# Wired_Mouse.net
KiCad netlist of a schematic drawn in EAGLE
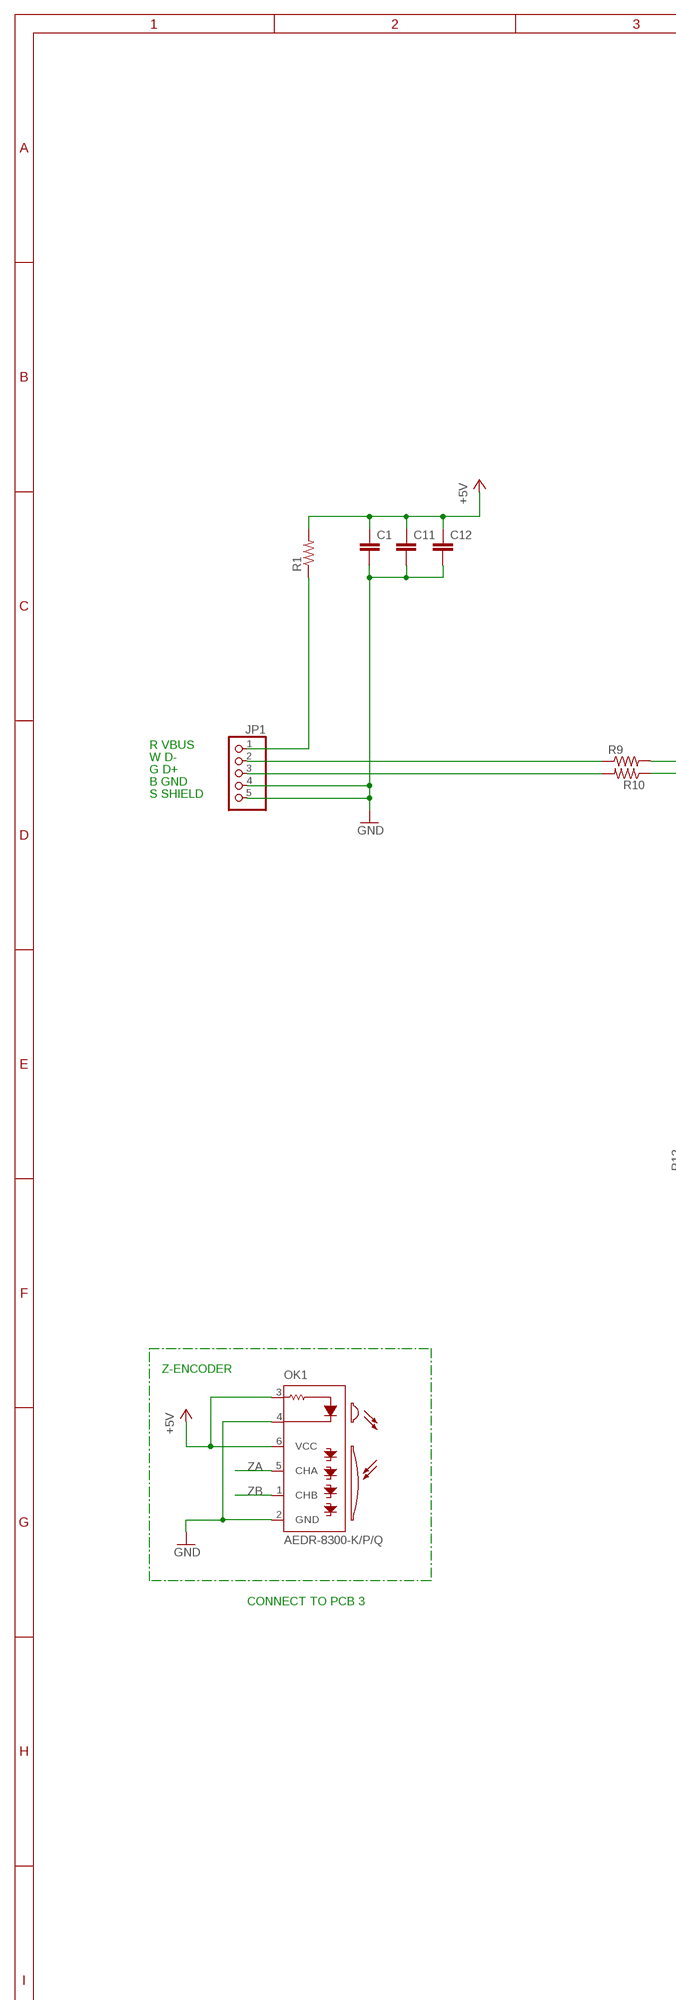
[diagram p0: schematic, sheet 1, part 1 of 2]
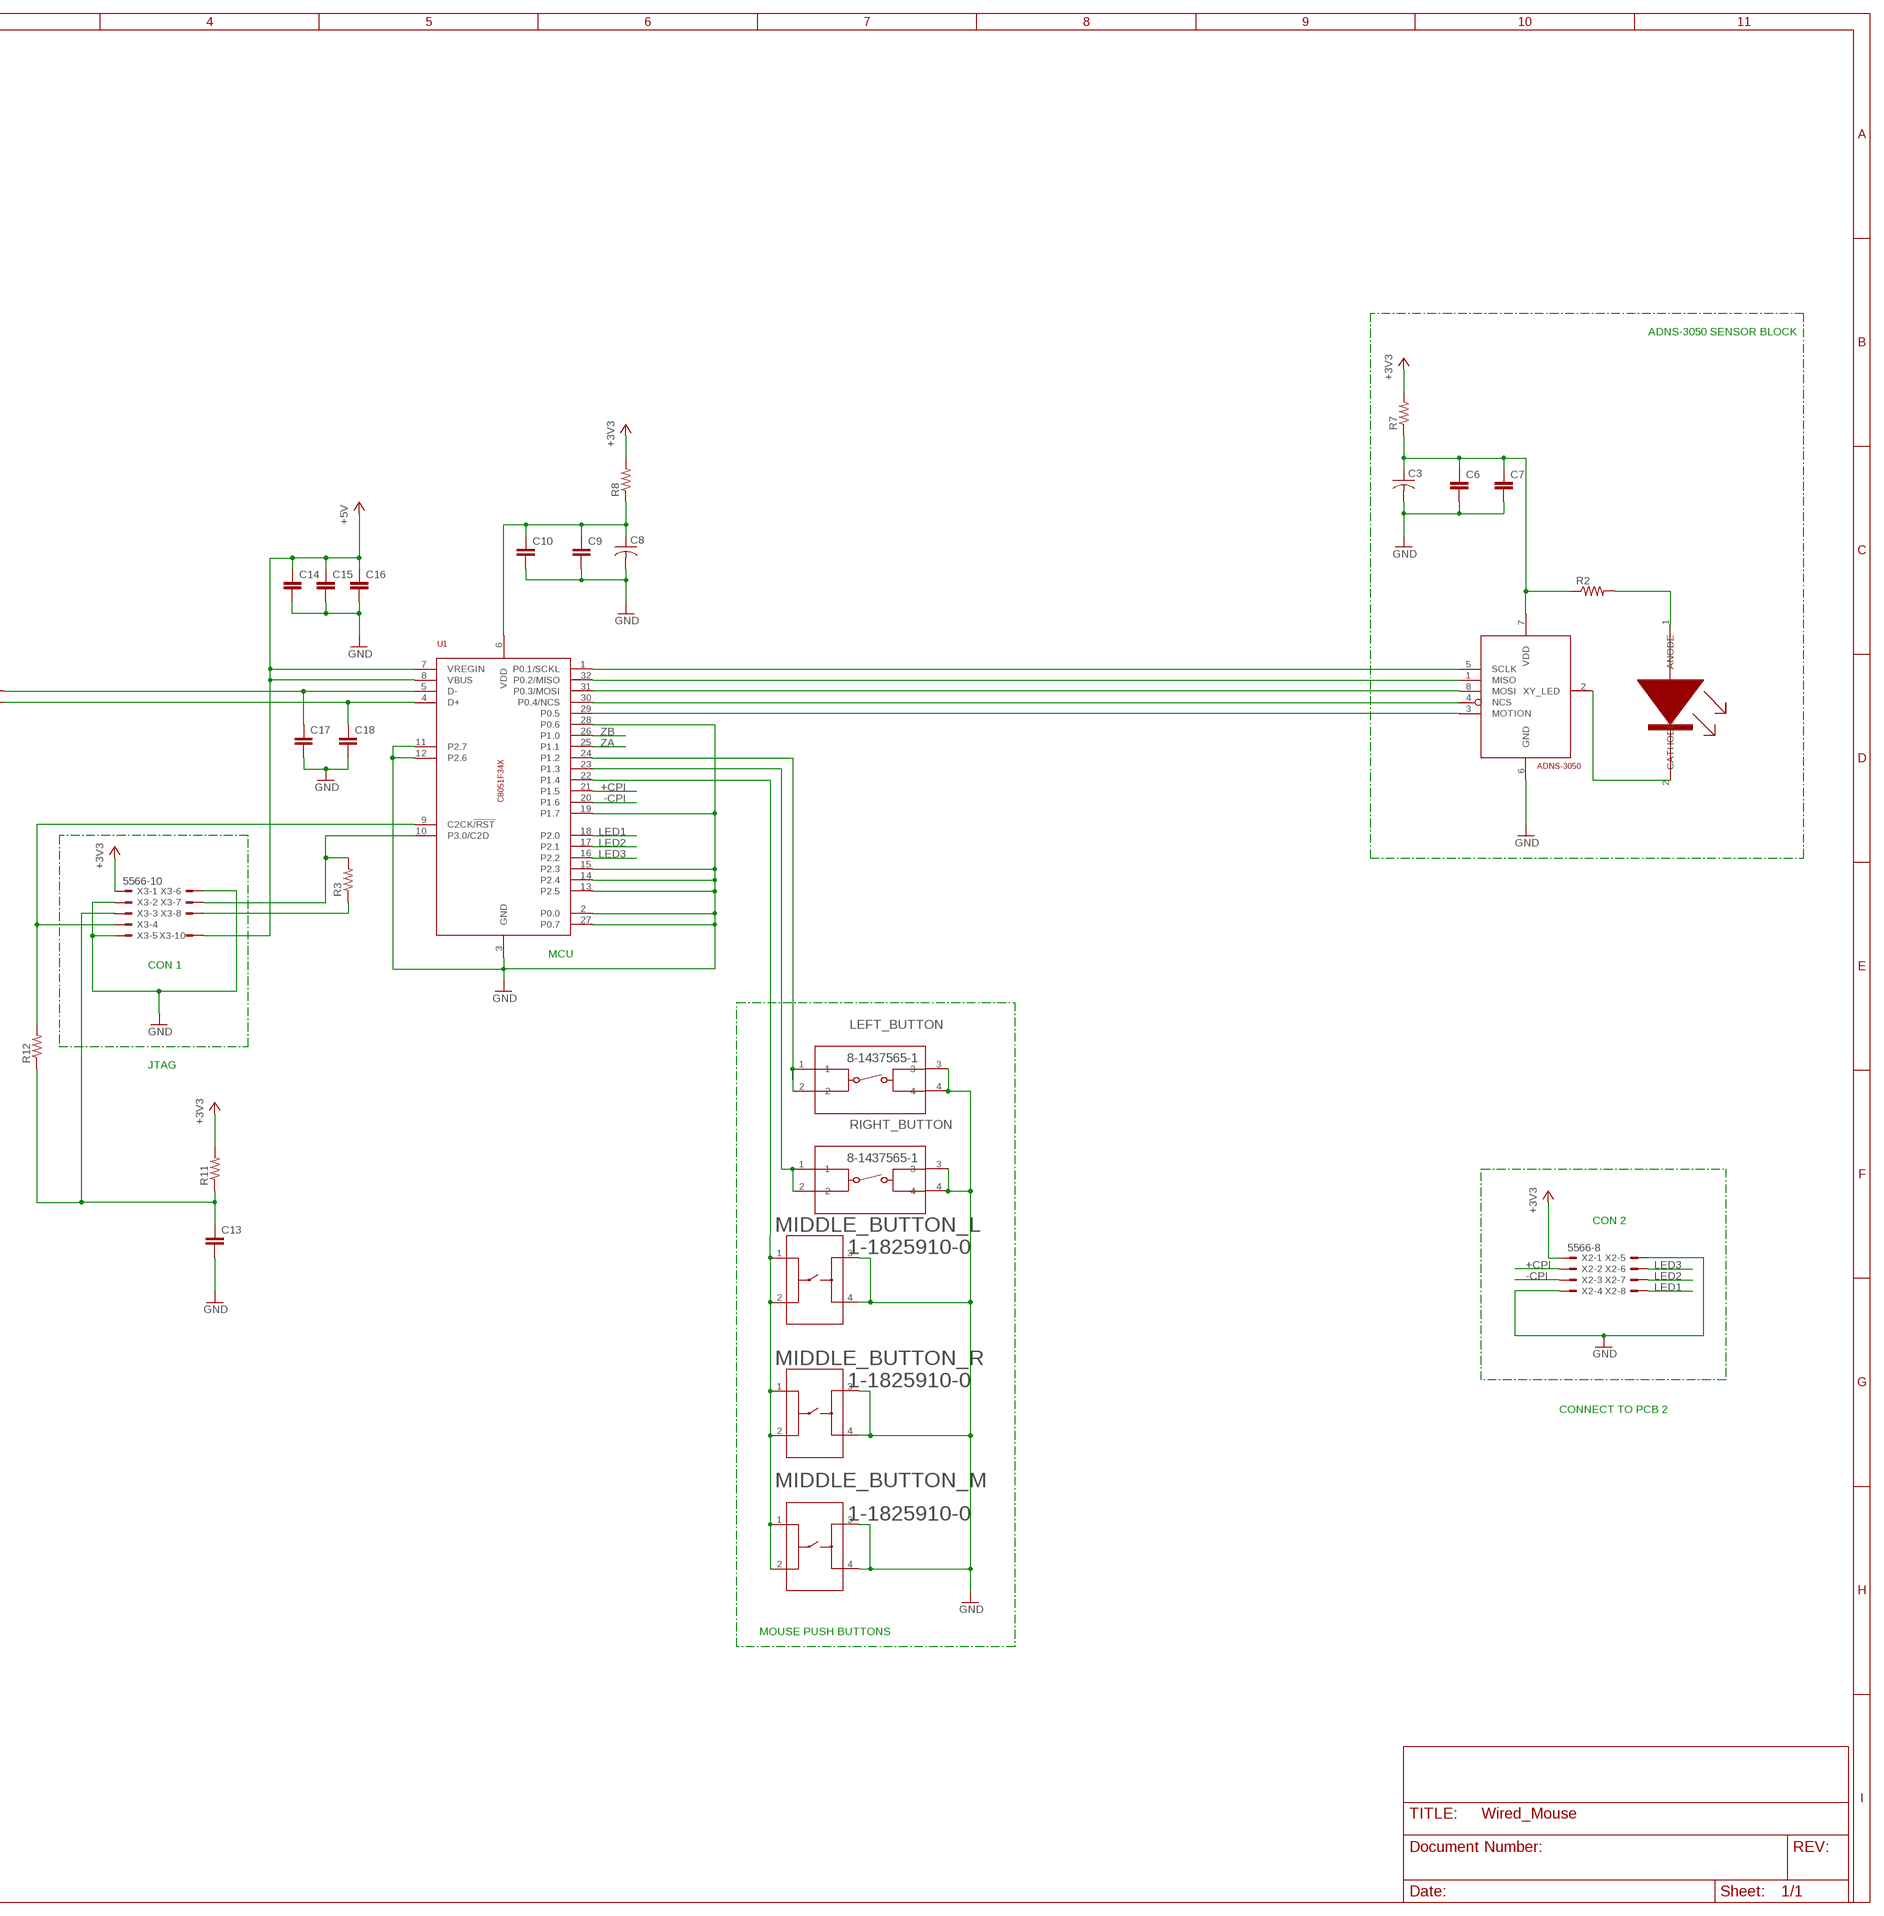
[diagram p1: schematic, sheet 1, part 2 of 2]

(export (version "E")
  (design (tool "Eeschema 10.0.6"))
  (components
    (comp (ref "C1")
      (value "C-EUC0201")
      (footprint "eagle-import:C0201")
      (libsource (lib "eagle-import") (part "C-EUC0201"))
    )
    (comp (ref "C3")
      (value "C-US025-025X050")
      (footprint "eagle-import:C025-025X050")
      (libsource (lib "eagle-import") (part "C-US025-025X050"))
    )
    (comp (ref "C6")
      (value "C-EUC0201")
      (footprint "eagle-import:C0201")
      (libsource (lib "eagle-import") (part "C-EUC0201"))
    )
    (comp (ref "C7")
      (value "C-EUC0201")
      (footprint "eagle-import:C0201")
      (libsource (lib "eagle-import") (part "C-EUC0201"))
    )
    (comp (ref "C8")
      (value "C-US025-025X050")
      (footprint "eagle-import:C025-025X050")
      (libsource (lib "eagle-import") (part "C-US025-025X050"))
    )
    (comp (ref "C9")
      (value "C-EUC0201")
      (footprint "eagle-import:C0201")
      (libsource (lib "eagle-import") (part "C-EUC0201"))
    )
    (comp (ref "C10")
      (value "C-EUC0201")
      (footprint "eagle-import:C0201")
      (libsource (lib "eagle-import") (part "C-EUC0201"))
    )
    (comp (ref "C11")
      (value "C-EUC0201")
      (footprint "eagle-import:C0201")
      (libsource (lib "eagle-import") (part "C-EUC0201"))
    )
    (comp (ref "C12")
      (value "C-EUC0201")
      (footprint "eagle-import:C0201")
      (libsource (lib "eagle-import") (part "C-EUC0201"))
    )
    (comp (ref "C13")
      (value "C-EUC0201")
      (footprint "eagle-import:C0201")
      (libsource (lib "eagle-import") (part "C-EUC0201"))
    )
    (comp (ref "C14")
      (value "C-EUC0201")
      (footprint "eagle-import:C0201")
      (libsource (lib "eagle-import") (part "C-EUC0201"))
    )
    (comp (ref "C15")
      (value "C-EUC0201")
      (footprint "eagle-import:C0201")
      (libsource (lib "eagle-import") (part "C-EUC0201"))
    )
    (comp (ref "C16")
      (value "C-EUC0201")
      (footprint "eagle-import:C0201")
      (libsource (lib "eagle-import") (part "C-EUC0201"))
    )
    (comp (ref "C17")
      (value "C-EUC0201")
      (footprint "eagle-import:C0201")
      (libsource (lib "eagle-import") (part "C-EUC0201"))
    )
    (comp (ref "C18")
      (value "C-EUC0201")
      (footprint "eagle-import:C0201")
      (libsource (lib "eagle-import") (part "C-EUC0201"))
    )
    (comp (ref "JP1")
      (value "PINHD-1X5/90")
      (footprint "eagle-import:1X05_90")
      (fields (field (name "SPICEPREFIX") "X"))
      (libsource (lib "eagle-import") (part "PINHD-1X5/90"))
    )
    (comp (ref "LEFT_BUTTON")
      (value "8-1437565-1")
      (footprint "eagle-import:SW4_1437565")
      (fields (field (name "COPYRIGHT") "Copyright (C) 2016 Accelerated Designs. All rights reserved"))
      (libsource (lib "eagle-import") (part "8-1437565-1"))
    )
    (comp (ref "MIDDLE_BUTTON_L")
      (value "1-1825910-0")
      (footprint "eagle-import:SWITCH_1-1825910-0")
      (fields (field (name "COPYRIGHT") "Copyright (C) 2016 Accelerated Designs. All rights reserved"))
      (libsource (lib "eagle-import") (part "1-1825910-0"))
    )
    (comp (ref "MIDDLE_BUTTON_M")
      (value "1-1825910-0")
      (footprint "eagle-import:SWITCH_1-1825910-0")
      (fields (field (name "COPYRIGHT") "Copyright (C) 2016 Accelerated Designs. All rights reserved"))
      (libsource (lib "eagle-import") (part "1-1825910-0"))
    )
    (comp (ref "MIDDLE_BUTTON_R")
      (value "1-1825910-0")
      (footprint "eagle-import:SWITCH_1-1825910-0")
      (fields (field (name "COPYRIGHT") "Copyright (C) 2016 Accelerated Designs. All rights reserved"))
      (libsource (lib "eagle-import") (part "1-1825910-0"))
    )
    (comp (ref "OK1")
      (value "AEDR-8300-K/P/Q")
      (footprint "eagle-import:AEDR-8300")
      (fields
        (field (name "MF") "AGILENT TECHNOLOGIES")
        (field (name "MPN") "AEDR-8300-1P2")
        (field (name "SPICEPREFIX") "X")
      )
      (libsource (lib "eagle-import") (part "AEDR-8300-K/P/Q"))
    )
    (comp (ref "R1")
      (value "R-US_0204/7")
      (footprint "eagle-import:0204_7")
      (libsource (lib "eagle-import") (part "R-US_0204/7"))
    )
    (comp (ref "R2")
      (value "R-US_0204/7")
      (footprint "eagle-import:0204_7")
      (libsource (lib "eagle-import") (part "R-US_0204/7"))
    )
    (comp (ref "R3")
      (value "R-US_0204/7")
      (footprint "eagle-import:0204_7")
      (libsource (lib "eagle-import") (part "R-US_0204/7"))
    )
    (comp (ref "R7")
      (value "R-US_0204/7")
      (footprint "eagle-import:0204_7")
      (libsource (lib "eagle-import") (part "R-US_0204/7"))
    )
    (comp (ref "R8")
      (value "R-US_0204/7")
      (footprint "eagle-import:0204_7")
      (libsource (lib "eagle-import") (part "R-US_0204/7"))
    )
    (comp (ref "R9")
      (value "R-US_0204/7")
      (footprint "eagle-import:0204_7")
      (libsource (lib "eagle-import") (part "R-US_0204/7"))
    )
    (comp (ref "R10")
      (value "R-US_0204/7")
      (footprint "eagle-import:0204_7")
      (libsource (lib "eagle-import") (part "R-US_0204/7"))
    )
    (comp (ref "R11")
      (value "R-US_0204/7")
      (footprint "eagle-import:0204_7")
      (libsource (lib "eagle-import") (part "R-US_0204/7"))
    )
    (comp (ref "R12")
      (value "R-US_0204/7")
      (footprint "eagle-import:0204_7")
      (libsource (lib "eagle-import") (part "R-US_0204/7"))
    )
    (comp (ref "RIGHT_BUTTON")
      (value "8-1437565-1")
      (footprint "eagle-import:SW4_1437565")
      (fields (field (name "COPYRIGHT") "Copyright (C) 2016 Accelerated Designs. All rights reserved"))
      (libsource (lib "eagle-import") (part "8-1437565-1"))
    )
    (comp (ref "U$1")
      (value "ADNS_3050THROUGH_HOLE")
      (footprint "eagle-import:DIP1279W50P200L985H450Q8B")
      (fields (field (name "SPICEPREFIX") "X"))
      (libsource (lib "eagle-import") (part "ADNS_3050THROUGH_HOLE"))
    )
    (comp (ref "U$2")
      (value "C8051F34XSURFACE-MOUNT")
      (footprint "eagle-import:QFP80P900X900X160-32N")
      (fields (field (name "SPICEPREFIX") "X"))
      (libsource (lib "eagle-import") (part "C8051F34XSURFACE-MOUNT"))
    )
    (comp (ref "U$3")
      (value "HLMP-EGXX_LEDTHROUGH_HOLE")
      (footprint "eagle-import:LEDRD254W50D500H871B")
      (fields (field (name "SPICEPREFIX") "B"))
      (libsource (lib "eagle-import") (part "HLMP-EGXX_LEDTHROUGH_HOLE"))
    )
    (comp (ref "X2")
      (value "5566-8")
      (footprint "eagle-import:5566-8")
      (fields (field (name "MF") "MOLEX") (field (name "SPICEPREFIX") "X"))
      (libsource (lib "eagle-import") (part "5566-8"))
    )
    (comp (ref "X3")
      (value "5566-10")
      (footprint "eagle-import:5566-10")
      (fields (field (name "MF") "MOLEX") (field (name "SPICEPREFIX") "X"))
      (libsource (lib "eagle-import") (part "5566-10"))
    )
  )
  (nets
    (net (code "1") (name "+3V3") (class "Default")
      (node (ref "R11") (pin "2") (pinfunction "2_2") (pintype "passive"))
      (node (ref "R7") (pin "2") (pinfunction "2_2") (pintype "passive"))
      (node (ref "R8") (pin "2") (pinfunction "2_2") (pintype "passive"))
      (node (ref "X2") (pin "1") (pinfunction "S_1") (pintype "passive"))
      (node (ref "X3") (pin "1") (pinfunction "S_1") (pintype "passive"))
    )
    (net (code "2") (name "+5V") (class "Default")
      (node (ref "C1") (pin "1") (pinfunction "1_1") (pintype "passive"))
      (node (ref "C11") (pin "1") (pinfunction "1_1") (pintype "passive"))
      (node (ref "C12") (pin "1") (pinfunction "1_1") (pintype "passive"))
      (node (ref "C14") (pin "1") (pinfunction "1_1") (pintype "passive"))
      (node (ref "C15") (pin "1") (pinfunction "1_1") (pintype "passive"))
      (node (ref "C16") (pin "1") (pinfunction "1_1") (pintype "passive"))
      (node (ref "OK1") (pin "3") (pinfunction "A_3") (pintype "passive"))
      (node (ref "OK1") (pin "6") (pinfunction "VCC_6") (pintype "passive"))
      (node (ref "R1") (pin "2") (pinfunction "2_2") (pintype "passive"))
      (node (ref "U$2") (pin "7") (pinfunction "VREGIN_7") (pintype "bidirectional"))
      (node (ref "U$2") (pin "8") (pinfunction "VBUS_8") (pintype "bidirectional"))
      (node (ref "X3") (pin "10") (pinfunction "S_10") (pintype "passive"))
    )
    (net (code "3") (name "/+CPI") (class "Default")
      (node (ref "U$2") (pin "21") (pinfunction "P1.5_21") (pintype "bidirectional"))
      (node (ref "X2") (pin "2") (pinfunction "S_2") (pintype "passive"))
    )
    (net (code "4") (name "/-CPI") (class "Default")
      (node (ref "U$2") (pin "20") (pinfunction "P1.6_20") (pintype "bidirectional"))
      (node (ref "X2") (pin "3") (pinfunction "S_3") (pintype "passive"))
    )
    (net (code "5") (name "/LED1") (class "Default")
      (node (ref "U$2") (pin "18") (pinfunction "P2.0_18") (pintype "bidirectional"))
      (node (ref "X2") (pin "8") (pinfunction "S_8") (pintype "passive"))
    )
    (net (code "6") (name "/LED2") (class "Default")
      (node (ref "U$2") (pin "17") (pinfunction "P2.1_17") (pintype "bidirectional"))
      (node (ref "X2") (pin "7") (pinfunction "S_7") (pintype "passive"))
    )
    (net (code "7") (name "/LED3") (class "Default")
      (node (ref "U$2") (pin "16") (pinfunction "P2.2_16") (pintype "bidirectional"))
      (node (ref "X2") (pin "6") (pinfunction "S_6") (pintype "passive"))
    )
    (net (code "8") (name "/ZA") (class "Default")
      (node (ref "OK1") (pin "5") (pinfunction "CHA_5") (pintype "passive"))
      (node (ref "U$2") (pin "25") (pinfunction "P1.1_25") (pintype "bidirectional"))
    )
    (net (code "9") (name "/ZB") (class "Default")
      (node (ref "OK1") (pin "1") (pinfunction "CHB_1") (pintype "passive"))
      (node (ref "U$2") (pin "26") (pinfunction "P1.0_26") (pintype "bidirectional"))
    )
    (net (code "10") (name "GND") (class "Default")
      (node (ref "C1") (pin "2") (pinfunction "2_2") (pintype "passive"))
      (node (ref "C10") (pin "2") (pinfunction "2_2") (pintype "passive"))
      (node (ref "C11") (pin "2") (pinfunction "2_2") (pintype "passive"))
      (node (ref "C12") (pin "2") (pinfunction "2_2") (pintype "passive"))
      (node (ref "C13") (pin "2") (pinfunction "2_2") (pintype "passive"))
      (node (ref "C14") (pin "2") (pinfunction "2_2") (pintype "passive"))
      (node (ref "C15") (pin "2") (pinfunction "2_2") (pintype "passive"))
      (node (ref "C16") (pin "2") (pinfunction "2_2") (pintype "passive"))
      (node (ref "C17") (pin "2") (pinfunction "2_2") (pintype "passive"))
      (node (ref "C18") (pin "2") (pinfunction "2_2") (pintype "passive"))
      (node (ref "C3") (pin "2") (pinfunction "2_2") (pintype "passive"))
      (node (ref "C6") (pin "2") (pinfunction "2_2") (pintype "passive"))
      (node (ref "C7") (pin "2") (pinfunction "2_2") (pintype "passive"))
      (node (ref "C8") (pin "2") (pinfunction "2_2") (pintype "passive"))
      (node (ref "C9") (pin "2") (pinfunction "2_2") (pintype "passive"))
      (node (ref "JP1") (pin "4") (pinfunction "4_4") (pintype "passive"))
      (node (ref "JP1") (pin "5") (pinfunction "5_5") (pintype "passive"))
      (node (ref "LEFT_BUTTON") (pin "3") (pinfunction "3_3") (pintype "passive"))
      (node (ref "LEFT_BUTTON") (pin "4") (pinfunction "4_4") (pintype "passive"))
      (node (ref "MIDDLE_BUTTON_L") (pin "3") (pinfunction "3_3") (pintype "passive"))
      (node (ref "MIDDLE_BUTTON_L") (pin "4") (pinfunction "4_4") (pintype "passive"))
      (node (ref "MIDDLE_BUTTON_M") (pin "3") (pinfunction "3_3") (pintype "passive"))
      (node (ref "MIDDLE_BUTTON_M") (pin "4") (pinfunction "4_4") (pintype "passive"))
      (node (ref "MIDDLE_BUTTON_R") (pin "3") (pinfunction "3_3") (pintype "passive"))
      (node (ref "MIDDLE_BUTTON_R") (pin "4") (pinfunction "4_4") (pintype "passive"))
      (node (ref "OK1") (pin "2") (pinfunction "GND_2") (pintype "passive"))
      (node (ref "OK1") (pin "4") (pinfunction "C_4") (pintype "passive"))
      (node (ref "RIGHT_BUTTON") (pin "3") (pinfunction "3_3") (pintype "passive"))
      (node (ref "RIGHT_BUTTON") (pin "4") (pinfunction "4_4") (pintype "passive"))
      (node (ref "U$1") (pin "6") (pinfunction "GND_6") (pintype "bidirectional"))
      (node (ref "U$2") (pin "11") (pinfunction "P2.7_11") (pintype "bidirectional"))
      (node (ref "U$2") (pin "12") (pinfunction "P2.6_12") (pintype "bidirectional"))
      (node (ref "U$2") (pin "13") (pinfunction "P2.5_13") (pintype "bidirectional"))
      (node (ref "U$2") (pin "14") (pinfunction "P2.4_14") (pintype "bidirectional"))
      (node (ref "U$2") (pin "15") (pinfunction "P2.3_15") (pintype "bidirectional"))
      (node (ref "U$2") (pin "19") (pinfunction "P1.7_19") (pintype "bidirectional"))
      (node (ref "U$2") (pin "2") (pinfunction "P0.0_2") (pintype "bidirectional"))
      (node (ref "U$2") (pin "27") (pinfunction "P0.7_27") (pintype "bidirectional"))
      (node (ref "U$2") (pin "28") (pinfunction "P0.6_28") (pintype "bidirectional"))
      (node (ref "U$2") (pin "3") (pinfunction "GND_3") (pintype "bidirectional"))
      (node (ref "X2") (pin "4") (pinfunction "S_4") (pintype "passive"))
      (node (ref "X2") (pin "5") (pinfunction "S_5") (pintype "passive"))
      (node (ref "X3") (pin "2") (pinfunction "S_2") (pintype "passive"))
      (node (ref "X3") (pin "5") (pinfunction "S_5") (pintype "passive"))
      (node (ref "X3") (pin "6") (pinfunction "S_6") (pintype "passive"))
    )
    (net (code "11") (name "Net-(JP1-Pad1)") (class "Default")
      (node (ref "JP1") (pin "1") (pinfunction "1_1") (pintype "passive"))
      (node (ref "R1") (pin "1") (pinfunction "1_1") (pintype "passive"))
    )
    (net (code "12") (name "Net-(JP1-Pad2)") (class "Default")
      (node (ref "JP1") (pin "2") (pinfunction "2_2") (pintype "passive"))
      (node (ref "R9") (pin "1") (pinfunction "1_1") (pintype "passive"))
    )
    (net (code "13") (name "Net-(JP1-Pad3)") (class "Default")
      (node (ref "JP1") (pin "3") (pinfunction "3_3") (pintype "passive"))
      (node (ref "R10") (pin "2") (pinfunction "2_2") (pintype "passive"))
    )
    (net (code "14") (name "Net-(U$1-MISO)") (class "Default")
      (node (ref "U$1") (pin "1") (pinfunction "MISO_1") (pintype "bidirectional"))
      (node (ref "U$2") (pin "32") (pinfunction "P0.2/MISO_32") (pintype "bidirectional"))
    )
    (net (code "15") (name "Net-(U$1-MOSI)") (class "Default")
      (node (ref "U$1") (pin "8") (pinfunction "MOSI_8") (pintype "bidirectional"))
      (node (ref "U$2") (pin "31") (pinfunction "P0.3/MOSI_31") (pintype "bidirectional"))
    )
    (net (code "16") (name "Net-(U$1-MOTION)") (class "Default")
      (node (ref "U$1") (pin "3") (pinfunction "MOTION_3") (pintype "bidirectional"))
      (node (ref "U$2") (pin "29") (pinfunction "P0.5_29") (pintype "bidirectional"))
    )
    (net (code "17") (name "Net-(U$1-NCS)") (class "Default")
      (node (ref "U$1") (pin "4") (pinfunction "NCS_4") (pintype "bidirectional"))
      (node (ref "U$2") (pin "30") (pinfunction "P0.4/NCS_30") (pintype "bidirectional"))
    )
    (net (code "18") (name "Net-(U$1-SCLK)") (class "Default")
      (node (ref "U$1") (pin "5") (pinfunction "SCLK_5") (pintype "bidirectional"))
      (node (ref "U$2") (pin "1") (pinfunction "P0.1/SCKL_1") (pintype "bidirectional"))
    )
    (net (code "19") (name "Net-(U$1-VDD)") (class "Default")
      (node (ref "C3") (pin "1") (pinfunction "1_1") (pintype "passive"))
      (node (ref "C6") (pin "1") (pinfunction "1_1") (pintype "passive"))
      (node (ref "C7") (pin "1") (pinfunction "1_1") (pintype "passive"))
      (node (ref "R2") (pin "1") (pinfunction "1_1") (pintype "passive"))
      (node (ref "R7") (pin "1") (pinfunction "1_1") (pintype "passive"))
      (node (ref "U$1") (pin "7") (pinfunction "VDD_7") (pintype "bidirectional"))
    )
    (net (code "20") (name "Net-(U$1-XY_LED)") (class "Default")
      (node (ref "U$1") (pin "2") (pinfunction "XY_LED_2") (pintype "bidirectional"))
      (node (ref "U$3") (pin "2") (pinfunction "CATHODE_2") (pintype "bidirectional"))
    )
    (net (code "21") (name "Net-(U$2-C2CK~{{slash}RST})") (class "Default")
      (node (ref "R12") (pin "2") (pinfunction "2_2") (pintype "passive"))
      (node (ref "U$2") (pin "9") (pinfunction "C2CK~{/RST}_9") (pintype "bidirectional"))
      (node (ref "X3") (pin "4") (pinfunction "S_4") (pintype "passive"))
    )
    (net (code "22") (name "Net-(U$2-D+)") (class "Default")
      (node (ref "C18") (pin "1") (pinfunction "1_1") (pintype "passive"))
      (node (ref "R10") (pin "1") (pinfunction "1_1") (pintype "passive"))
      (node (ref "U$2") (pin "4") (pinfunction "D+_4") (pintype "bidirectional"))
    )
    (net (code "23") (name "Net-(U$2-D-)") (class "Default")
      (node (ref "C17") (pin "1") (pinfunction "1_1") (pintype "passive"))
      (node (ref "R9") (pin "2") (pinfunction "2_2") (pintype "passive"))
      (node (ref "U$2") (pin "5") (pinfunction "D-_5") (pintype "bidirectional"))
    )
    (net (code "24") (name "Net-(U$2-P1.2)") (class "Default")
      (node (ref "LEFT_BUTTON") (pin "1") (pinfunction "1_1") (pintype "passive"))
      (node (ref "LEFT_BUTTON") (pin "2") (pinfunction "2_2") (pintype "passive"))
      (node (ref "U$2") (pin "24") (pinfunction "P1.2_24") (pintype "bidirectional"))
    )
    (net (code "25") (name "Net-(U$2-P1.3)") (class "Default")
      (node (ref "RIGHT_BUTTON") (pin "1") (pinfunction "1_1") (pintype "passive"))
      (node (ref "RIGHT_BUTTON") (pin "2") (pinfunction "2_2") (pintype "passive"))
      (node (ref "U$2") (pin "23") (pinfunction "P1.3_23") (pintype "bidirectional"))
    )
    (net (code "26") (name "Net-(U$2-P1.4)") (class "Default")
      (node (ref "MIDDLE_BUTTON_L") (pin "1") (pinfunction "1_1") (pintype "passive"))
      (node (ref "MIDDLE_BUTTON_L") (pin "2") (pinfunction "2_2") (pintype "passive"))
      (node (ref "MIDDLE_BUTTON_M") (pin "1") (pinfunction "1_1") (pintype "passive"))
      (node (ref "MIDDLE_BUTTON_M") (pin "2") (pinfunction "2_2") (pintype "passive"))
      (node (ref "MIDDLE_BUTTON_R") (pin "1") (pinfunction "1_1") (pintype "passive"))
      (node (ref "MIDDLE_BUTTON_R") (pin "2") (pinfunction "2_2") (pintype "passive"))
      (node (ref "U$2") (pin "22") (pinfunction "P1.4_22") (pintype "bidirectional"))
    )
    (net (code "27") (name "Net-(U$2-P3.0{slash}C2D)") (class "Default")
      (node (ref "R3") (pin "2") (pinfunction "2_2") (pintype "passive"))
      (node (ref "U$2") (pin "10") (pinfunction "P3.0/C2D_10") (pintype "bidirectional"))
      (node (ref "X3") (pin "7") (pinfunction "S_7") (pintype "passive"))
    )
    (net (code "28") (name "Net-(U$2-VDD)") (class "Default")
      (node (ref "C10") (pin "1") (pinfunction "1_1") (pintype "passive"))
      (node (ref "C8") (pin "1") (pinfunction "1_1") (pintype "passive"))
      (node (ref "C9") (pin "1") (pinfunction "1_1") (pintype "passive"))
      (node (ref "R8") (pin "1") (pinfunction "1_1") (pintype "passive"))
      (node (ref "U$2") (pin "6") (pinfunction "VDD_6") (pintype "bidirectional"))
    )
    (net (code "29") (name "Net-(U$3-ANODE)") (class "Default")
      (node (ref "R2") (pin "2") (pinfunction "2_2") (pintype "passive"))
      (node (ref "U$3") (pin "1") (pinfunction "ANODE_1") (pintype "bidirectional"))
    )
    (net (code "30") (name "Net-(X3D-S)") (class "Default")
      (node (ref "C13") (pin "1") (pinfunction "1_1") (pintype "passive"))
      (node (ref "R11") (pin "1") (pinfunction "1_1") (pintype "passive"))
      (node (ref "R12") (pin "1") (pinfunction "1_1") (pintype "passive"))
      (node (ref "X3") (pin "3") (pinfunction "S_3") (pintype "passive"))
    )
    (net (code "31") (name "Net-(X3I-S)") (class "Default")
      (node (ref "R3") (pin "1") (pinfunction "1_1") (pintype "passive"))
      (node (ref "X3") (pin "8") (pinfunction "S_8") (pintype "passive"))
    )
  )
)
